# PCB_2d.net
KiCad netlist of a schematic drawn in EAGLE
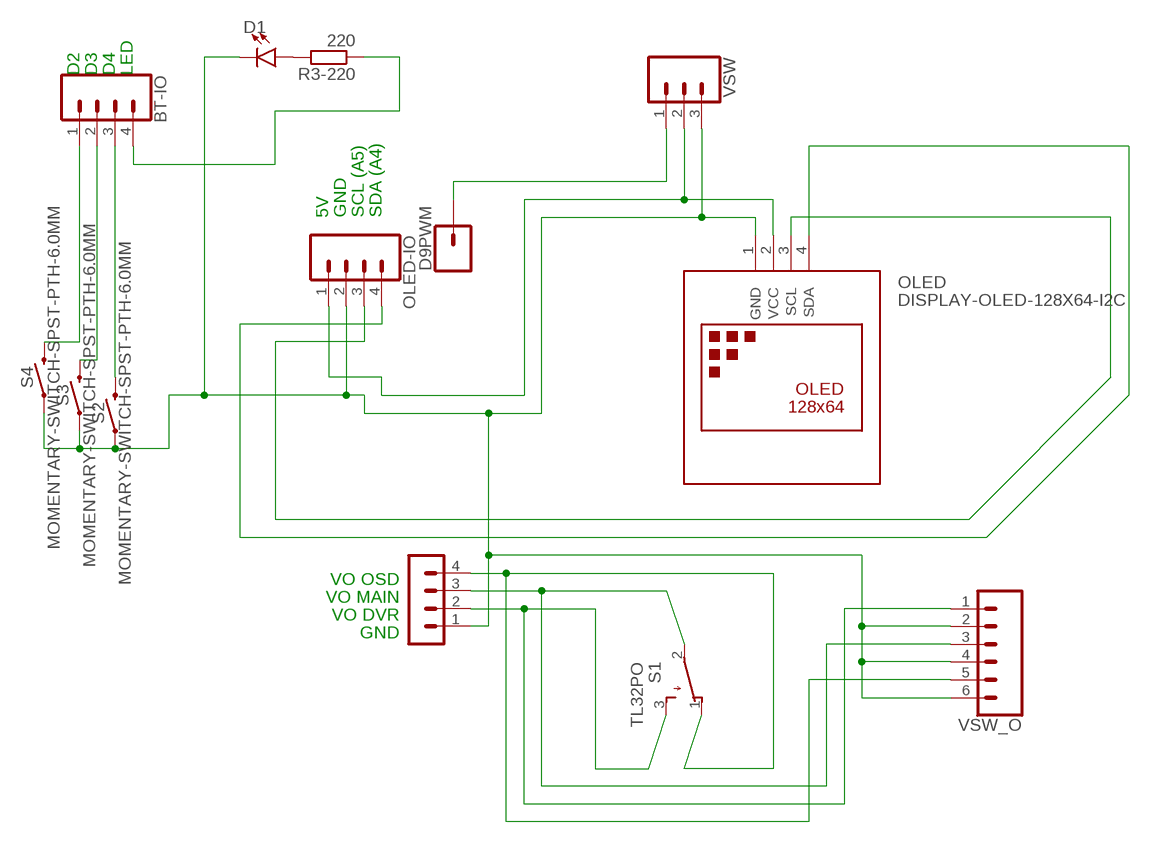
[diagram p0: schematic, sheet 1]

(export (version "E")
  (design (tool "Eeschema 10.0.6"))
  (components
    (comp (ref "BT-IO")
      (value "CONN_04")
      (footprint "eagle-import:1X04")
      (libsource (lib "eagle-import") (part "CONN_04"))
    )
    (comp (ref "D1")
      (value "LED3MM")
      (footprint "eagle-import:LED_3MM")
      (libsource (lib "eagle-import") (part "LED3MM"))
    )
    (comp (ref "D9PWM")
      (value "CONN_01")
      (footprint "eagle-import:1X01")
      (libsource (lib "eagle-import") (part "CONN_01"))
    )
    (comp (ref "IO3")
      (value "MA04-1")
      (footprint "eagle-import:MA04-1")
      (libsource (lib "eagle-import") (part "MA04-1"))
    )
    (comp (ref "OLED")
      (value "DISPLAY-OLED-128X64-I2C")
      (footprint "eagle-import:DISPLAY-OLED-128X64-I2C")
      (libsource (lib "eagle-import") (part "DISPLAY-OLED-128X64-I2C"))
    )
    (comp (ref "OLED-IO")
      (value "CONN_04")
      (footprint "eagle-import:1X04")
      (libsource (lib "eagle-import") (part "CONN_04"))
    )
    (comp (ref "R3-220")
      (value "220")
      (footprint "eagle-import:R1206")
      (libsource (lib "eagle-import") (part "R-EU_R1206"))
    )
    (comp (ref "S1")
      (value "TL32PO")
      (footprint "eagle-import:TL3XPO")
      (libsource (lib "eagle-import") (part "TL32PO"))
    )
    (comp (ref "S2")
      (value "MOMENTARY-SWITCH-SPST-PTH-6.0MM")
      (footprint "eagle-import:TACTILE_SWITCH_PTH_6.0MM")
      (libsource (lib "eagle-import") (part "MOMENTARY-SWITCH-SPST-PTH-6.0MM"))
    )
    (comp (ref "S3")
      (value "MOMENTARY-SWITCH-SPST-PTH-6.0MM")
      (footprint "eagle-import:TACTILE_SWITCH_PTH_6.0MM")
      (libsource (lib "eagle-import") (part "MOMENTARY-SWITCH-SPST-PTH-6.0MM"))
    )
    (comp (ref "S4")
      (value "MOMENTARY-SWITCH-SPST-PTH-6.0MM")
      (footprint "eagle-import:TACTILE_SWITCH_PTH_6.0MM")
      (libsource (lib "eagle-import") (part "MOMENTARY-SWITCH-SPST-PTH-6.0MM"))
    )
    (comp (ref "VSW")
      (value "CONN_03")
      (footprint "eagle-import:1X03")
      (libsource (lib "eagle-import") (part "CONN_03"))
    )
    (comp (ref "VSW_O")
      (value "CONN_06SILK_FEMALE_PTH")
      (footprint "eagle-import:1X06")
      (libsource (lib "eagle-import") (part "CONN_06SILK_FEMALE_PTH"))
    )
  )
  (nets
    (net (code "1") (name "Net-(BT-IO-Pad4)") (class "Default")
      (node (ref "BT-IO") (pin "4") (pinfunction "4_4") (pintype "passive"))
      (node (ref "R3-220") (pin "1") (pinfunction "1_1") (pintype "passive"))
    )
    (net (code "2") (name "Net-(D1-C)") (class "Default")
      (node (ref "D1") (pin "K") (pinfunction "C_K") (pintype "passive"))
      (node (ref "IO3") (pin "1") (pinfunction "1_1") (pintype "passive"))
      (node (ref "OLED") (pin "1") (pinfunction "GND_1") (pintype "power_in"))
      (node (ref "OLED-IO") (pin "2") (pinfunction "2_2") (pintype "passive"))
      (node (ref "S2") (pin "1") (pinfunction "1_1") (pintype "passive"))
      (node (ref "S3") (pin "1") (pinfunction "1_1") (pintype "passive"))
      (node (ref "S4") (pin "1") (pinfunction "1_1") (pintype "passive"))
      (node (ref "VSW") (pin "3") (pinfunction "3_3") (pintype "passive"))
      (node (ref "VSW_O") (pin "2") (pinfunction "2_2") (pintype "passive"))
      (node (ref "VSW_O") (pin "4") (pinfunction "4_4") (pintype "passive"))
      (node (ref "VSW_O") (pin "6") (pinfunction "6_6") (pintype "passive"))
    )
    (net (code "3") (name "Net-(D1-PadA)") (class "Default")
      (node (ref "D1") (pin "A") (pinfunction "A_A") (pintype "passive"))
      (node (ref "R3-220") (pin "2") (pinfunction "2_2") (pintype "passive"))
    )
    (net (code "4") (name "Net-(D9PWM-Pad1)") (class "Default")
      (node (ref "D9PWM") (pin "1") (pinfunction "1_1") (pintype "passive"))
      (node (ref "VSW") (pin "1") (pinfunction "1_1") (pintype "passive"))
    )
    (net (code "5") (name "Net-(OLED-SCL)") (class "Default")
      (node (ref "OLED") (pin "3") (pinfunction "SCL_3") (pintype "bidirectional"))
      (node (ref "OLED-IO") (pin "3") (pinfunction "3_3") (pintype "passive"))
    )
    (net (code "6") (name "Net-(OLED-SDA)") (class "Default")
      (node (ref "OLED") (pin "4") (pinfunction "SDA_4") (pintype "bidirectional"))
      (node (ref "OLED-IO") (pin "4") (pinfunction "4_4") (pintype "passive"))
    )
    (net (code "7") (name "Net-(OLED-VCC)") (class "Default")
      (node (ref "OLED") (pin "2") (pinfunction "VCC_2") (pintype "power_in"))
      (node (ref "OLED-IO") (pin "1") (pinfunction "1_1") (pintype "passive"))
      (node (ref "VSW") (pin "2") (pinfunction "2_2") (pintype "passive"))
    )
    (net (code "8") (name "Net-(S1-O)") (class "Default")
      (node (ref "IO3") (pin "4") (pinfunction "4_4") (pintype "passive"))
      (node (ref "S1") (pin "1") (pinfunction "O_1") (pintype "passive"))
      (node (ref "VSW_O") (pin "5") (pinfunction "5_5") (pintype "passive"))
    )
    (net (code "9") (name "Net-(S1-P)") (class "Default")
      (node (ref "IO3") (pin "3") (pinfunction "3_3") (pintype "passive"))
      (node (ref "S1") (pin "2") (pinfunction "P_2") (pintype "passive"))
      (node (ref "VSW_O") (pin "3") (pinfunction "3_3") (pintype "passive"))
    )
    (net (code "10") (name "Net-(S1-S)") (class "Default")
      (node (ref "IO3") (pin "2") (pinfunction "2_2") (pintype "passive"))
      (node (ref "S1") (pin "3") (pinfunction "S_3") (pintype "passive"))
      (node (ref "VSW_O") (pin "1") (pinfunction "1_1") (pintype "passive"))
    )
    (net (code "11") (name "Net-(S2-2)") (class "Default")
      (node (ref "BT-IO") (pin "3") (pinfunction "3_3") (pintype "passive"))
      (node (ref "S2") (pin "3") (pinfunction "2_3") (pintype "passive"))
    )
    (net (code "12") (name "Net-(S3-2)") (class "Default")
      (node (ref "BT-IO") (pin "2") (pinfunction "2_2") (pintype "passive"))
      (node (ref "S3") (pin "3") (pinfunction "2_3") (pintype "passive"))
    )
    (net (code "13") (name "Net-(S4-2)") (class "Default")
      (node (ref "BT-IO") (pin "1") (pinfunction "1_1") (pintype "passive"))
      (node (ref "S4") (pin "3") (pinfunction "2_3") (pintype "passive"))
    )
  )
)
